# breakout.net
KiCad netlist of a schematic drawn in EAGLE
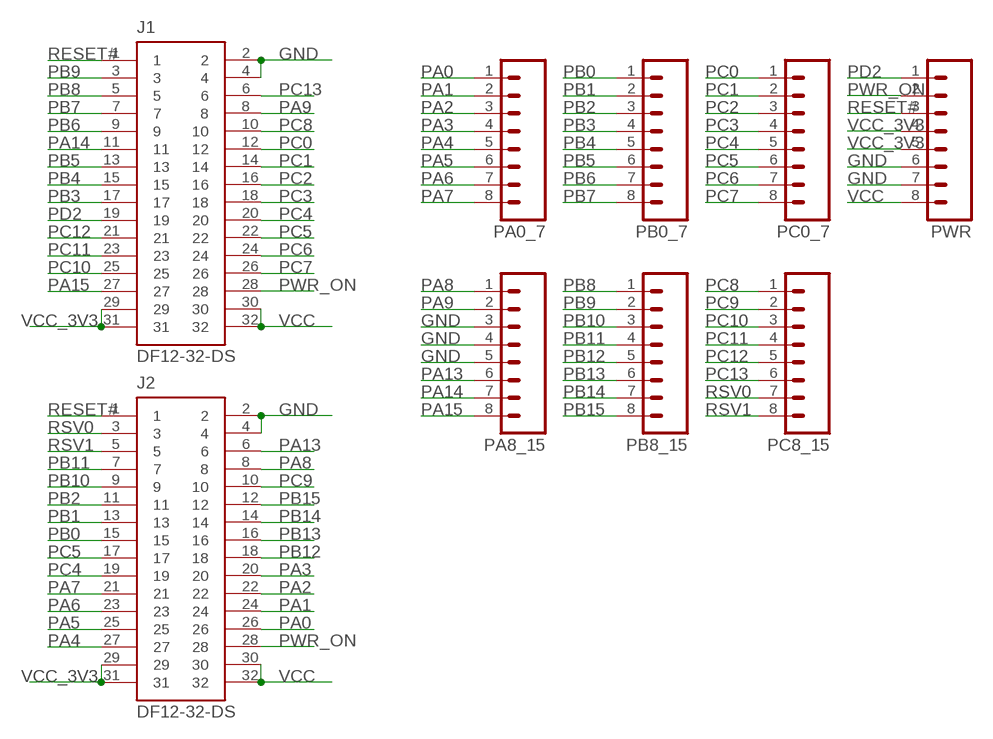
[diagram p0: schematic, sheet 1]

(export (version "E")
  (design (tool "Eeschema 10.0.6"))
  (components
    (comp (ref "J1")
      (value "DF12-32-DS")
      (footprint "eagle-import:DF12-32-DS")
      (fields (field (name "PARTNO") "AS-ITM-00012"))
      (libsource (lib "eagle-import") (part "AS-ITM-00012"))
    )
    (comp (ref "J2")
      (value "DF12-32-DS")
      (footprint "eagle-import:DF12-32-DS")
      (fields (field (name "PARTNO") "AS-ITM-00012"))
      (libsource (lib "eagle-import") (part "AS-ITM-00012"))
    )
    (comp (ref "PA0_7")
      (value "M08FEMALE_LOCK")
      (footprint "eagle-import:1X08_FEMALE_LOCK")
      (libsource (lib "eagle-import") (part "M08FEMALE_LOCK"))
    )
    (comp (ref "PA8_15")
      (value "M08FEMALE_LOCK")
      (footprint "eagle-import:1X08_FEMALE_LOCK")
      (libsource (lib "eagle-import") (part "M08FEMALE_LOCK"))
    )
    (comp (ref "PB0_7")
      (value "M08FEMALE_LOCK")
      (footprint "eagle-import:1X08_FEMALE_LOCK")
      (libsource (lib "eagle-import") (part "M08FEMALE_LOCK"))
    )
    (comp (ref "PB8_15")
      (value "M08FEMALE_LOCK")
      (footprint "eagle-import:1X08_FEMALE_LOCK")
      (libsource (lib "eagle-import") (part "M08FEMALE_LOCK"))
    )
    (comp (ref "PC0_7")
      (value "M08FEMALE_LOCK")
      (footprint "eagle-import:1X08_FEMALE_LOCK")
      (libsource (lib "eagle-import") (part "M08FEMALE_LOCK"))
    )
    (comp (ref "PC8_15")
      (value "M08FEMALE_LOCK")
      (footprint "eagle-import:1X08_FEMALE_LOCK")
      (libsource (lib "eagle-import") (part "M08FEMALE_LOCK"))
    )
    (comp (ref "PWR")
      (value "M08FEMALE_LOCK")
      (footprint "eagle-import:1X08_FEMALE_LOCK")
      (libsource (lib "eagle-import") (part "M08FEMALE_LOCK"))
    )
  )
  (nets
    (net (code "1") (name "/GND") (class "Default")
      (node (ref "J1") (pin "2") (pinfunction "2_2") (pintype "bidirectional"))
      (node (ref "J1") (pin "4") (pinfunction "4_4") (pintype "bidirectional"))
      (node (ref "J2") (pin "2") (pinfunction "2_2") (pintype "bidirectional"))
      (node (ref "J2") (pin "4") (pinfunction "4_4") (pintype "bidirectional"))
      (node (ref "PA8_15") (pin "3") (pinfunction "3_3") (pintype "passive"))
      (node (ref "PA8_15") (pin "4") (pinfunction "4_4") (pintype "passive"))
      (node (ref "PA8_15") (pin "5") (pinfunction "5_5") (pintype "passive"))
      (node (ref "PWR") (pin "6") (pinfunction "6_6") (pintype "passive"))
      (node (ref "PWR") (pin "7") (pinfunction "7_7") (pintype "passive"))
    )
    (net (code "2") (name "/PA0") (class "Default")
      (node (ref "J2") (pin "26") (pinfunction "26_26") (pintype "bidirectional"))
      (node (ref "PA0_7") (pin "1") (pinfunction "1_1") (pintype "passive"))
    )
    (net (code "3") (name "/PA1") (class "Default")
      (node (ref "J2") (pin "24") (pinfunction "24_24") (pintype "bidirectional"))
      (node (ref "PA0_7") (pin "2") (pinfunction "2_2") (pintype "passive"))
    )
    (net (code "4") (name "/PA2") (class "Default")
      (node (ref "J2") (pin "22") (pinfunction "22_22") (pintype "bidirectional"))
      (node (ref "PA0_7") (pin "3") (pinfunction "3_3") (pintype "passive"))
    )
    (net (code "5") (name "/PA3") (class "Default")
      (node (ref "J2") (pin "20") (pinfunction "20_20") (pintype "bidirectional"))
      (node (ref "PA0_7") (pin "4") (pinfunction "4_4") (pintype "passive"))
    )
    (net (code "6") (name "/PA4") (class "Default")
      (node (ref "J2") (pin "27") (pinfunction "27_27") (pintype "bidirectional"))
      (node (ref "PA0_7") (pin "5") (pinfunction "5_5") (pintype "passive"))
    )
    (net (code "7") (name "/PA5") (class "Default")
      (node (ref "J2") (pin "25") (pinfunction "25_25") (pintype "bidirectional"))
      (node (ref "PA0_7") (pin "6") (pinfunction "6_6") (pintype "passive"))
    )
    (net (code "8") (name "/PA6") (class "Default")
      (node (ref "J2") (pin "23") (pinfunction "23_23") (pintype "bidirectional"))
      (node (ref "PA0_7") (pin "7") (pinfunction "7_7") (pintype "passive"))
    )
    (net (code "9") (name "/PA7") (class "Default")
      (node (ref "J2") (pin "21") (pinfunction "21_21") (pintype "bidirectional"))
      (node (ref "PA0_7") (pin "8") (pinfunction "8_8") (pintype "passive"))
    )
    (net (code "10") (name "/PA8") (class "Default")
      (node (ref "J2") (pin "8") (pinfunction "8_8") (pintype "bidirectional"))
      (node (ref "PA8_15") (pin "1") (pinfunction "1_1") (pintype "passive"))
    )
    (net (code "11") (name "/PA9") (class "Default")
      (node (ref "J1") (pin "8") (pinfunction "8_8") (pintype "bidirectional"))
      (node (ref "PA8_15") (pin "2") (pinfunction "2_2") (pintype "passive"))
    )
    (net (code "12") (name "/PA13") (class "Default")
      (node (ref "J2") (pin "6") (pinfunction "6_6") (pintype "bidirectional"))
      (node (ref "PA8_15") (pin "6") (pinfunction "6_6") (pintype "passive"))
    )
    (net (code "13") (name "/PA14") (class "Default")
      (node (ref "J1") (pin "11") (pinfunction "11_11") (pintype "bidirectional"))
      (node (ref "PA8_15") (pin "7") (pinfunction "7_7") (pintype "passive"))
    )
    (net (code "14") (name "/PA15") (class "Default")
      (node (ref "J1") (pin "27") (pinfunction "27_27") (pintype "bidirectional"))
      (node (ref "PA8_15") (pin "8") (pinfunction "8_8") (pintype "passive"))
    )
    (net (code "15") (name "/PB0") (class "Default")
      (node (ref "J2") (pin "15") (pinfunction "15_15") (pintype "bidirectional"))
      (node (ref "PB0_7") (pin "1") (pinfunction "1_1") (pintype "passive"))
    )
    (net (code "16") (name "/PB1") (class "Default")
      (node (ref "J2") (pin "13") (pinfunction "13_13") (pintype "bidirectional"))
      (node (ref "PB0_7") (pin "2") (pinfunction "2_2") (pintype "passive"))
    )
    (net (code "17") (name "/PB2") (class "Default")
      (node (ref "J2") (pin "11") (pinfunction "11_11") (pintype "bidirectional"))
      (node (ref "PB0_7") (pin "3") (pinfunction "3_3") (pintype "passive"))
    )
    (net (code "18") (name "/PB3") (class "Default")
      (node (ref "J1") (pin "17") (pinfunction "17_17") (pintype "bidirectional"))
      (node (ref "PB0_7") (pin "4") (pinfunction "4_4") (pintype "passive"))
    )
    (net (code "19") (name "/PB4") (class "Default")
      (node (ref "J1") (pin "15") (pinfunction "15_15") (pintype "bidirectional"))
      (node (ref "PB0_7") (pin "5") (pinfunction "5_5") (pintype "passive"))
    )
    (net (code "20") (name "/PB5") (class "Default")
      (node (ref "J1") (pin "13") (pinfunction "13_13") (pintype "bidirectional"))
      (node (ref "PB0_7") (pin "6") (pinfunction "6_6") (pintype "passive"))
    )
    (net (code "21") (name "/PB6") (class "Default")
      (node (ref "J1") (pin "9") (pinfunction "9_9") (pintype "bidirectional"))
      (node (ref "PB0_7") (pin "7") (pinfunction "7_7") (pintype "passive"))
    )
    (net (code "22") (name "/PB7") (class "Default")
      (node (ref "J1") (pin "7") (pinfunction "7_7") (pintype "bidirectional"))
      (node (ref "PB0_7") (pin "8") (pinfunction "8_8") (pintype "passive"))
    )
    (net (code "23") (name "/PB8") (class "Default")
      (node (ref "J1") (pin "5") (pinfunction "5_5") (pintype "bidirectional"))
      (node (ref "PB8_15") (pin "1") (pinfunction "1_1") (pintype "passive"))
    )
    (net (code "24") (name "/PB9") (class "Default")
      (node (ref "J1") (pin "3") (pinfunction "3_3") (pintype "bidirectional"))
      (node (ref "PB8_15") (pin "2") (pinfunction "2_2") (pintype "passive"))
    )
    (net (code "25") (name "/PB10") (class "Default")
      (node (ref "J2") (pin "9") (pinfunction "9_9") (pintype "bidirectional"))
      (node (ref "PB8_15") (pin "3") (pinfunction "3_3") (pintype "passive"))
    )
    (net (code "26") (name "/PB11") (class "Default")
      (node (ref "J2") (pin "7") (pinfunction "7_7") (pintype "bidirectional"))
      (node (ref "PB8_15") (pin "4") (pinfunction "4_4") (pintype "passive"))
    )
    (net (code "27") (name "/PB12") (class "Default")
      (node (ref "J2") (pin "18") (pinfunction "18_18") (pintype "bidirectional"))
      (node (ref "PB8_15") (pin "5") (pinfunction "5_5") (pintype "passive"))
    )
    (net (code "28") (name "/PB13") (class "Default")
      (node (ref "J2") (pin "16") (pinfunction "16_16") (pintype "bidirectional"))
      (node (ref "PB8_15") (pin "6") (pinfunction "6_6") (pintype "passive"))
    )
    (net (code "29") (name "/PB14") (class "Default")
      (node (ref "J2") (pin "14") (pinfunction "14_14") (pintype "bidirectional"))
      (node (ref "PB8_15") (pin "7") (pinfunction "7_7") (pintype "passive"))
    )
    (net (code "30") (name "/PB15") (class "Default")
      (node (ref "J2") (pin "12") (pinfunction "12_12") (pintype "bidirectional"))
      (node (ref "PB8_15") (pin "8") (pinfunction "8_8") (pintype "passive"))
    )
    (net (code "31") (name "/PC0") (class "Default")
      (node (ref "J1") (pin "12") (pinfunction "12_12") (pintype "bidirectional"))
      (node (ref "PC0_7") (pin "1") (pinfunction "1_1") (pintype "passive"))
    )
    (net (code "32") (name "/PC1") (class "Default")
      (node (ref "J1") (pin "14") (pinfunction "14_14") (pintype "bidirectional"))
      (node (ref "PC0_7") (pin "2") (pinfunction "2_2") (pintype "passive"))
    )
    (net (code "33") (name "/PC2") (class "Default")
      (node (ref "J1") (pin "16") (pinfunction "16_16") (pintype "bidirectional"))
      (node (ref "PC0_7") (pin "3") (pinfunction "3_3") (pintype "passive"))
    )
    (net (code "34") (name "/PC3") (class "Default")
      (node (ref "J1") (pin "18") (pinfunction "18_18") (pintype "bidirectional"))
      (node (ref "PC0_7") (pin "4") (pinfunction "4_4") (pintype "passive"))
    )
    (net (code "35") (name "/PC4") (class "Default")
      (node (ref "J1") (pin "20") (pinfunction "20_20") (pintype "bidirectional"))
      (node (ref "J2") (pin "19") (pinfunction "19_19") (pintype "bidirectional"))
      (node (ref "PC0_7") (pin "5") (pinfunction "5_5") (pintype "passive"))
    )
    (net (code "36") (name "/PC5") (class "Default")
      (node (ref "J1") (pin "22") (pinfunction "22_22") (pintype "bidirectional"))
      (node (ref "J2") (pin "17") (pinfunction "17_17") (pintype "bidirectional"))
      (node (ref "PC0_7") (pin "6") (pinfunction "6_6") (pintype "passive"))
    )
    (net (code "37") (name "/PC6") (class "Default")
      (node (ref "J1") (pin "24") (pinfunction "24_24") (pintype "bidirectional"))
      (node (ref "PC0_7") (pin "7") (pinfunction "7_7") (pintype "passive"))
    )
    (net (code "38") (name "/PC7") (class "Default")
      (node (ref "J1") (pin "26") (pinfunction "26_26") (pintype "bidirectional"))
      (node (ref "PC0_7") (pin "8") (pinfunction "8_8") (pintype "passive"))
    )
    (net (code "39") (name "/PC8") (class "Default")
      (node (ref "J1") (pin "10") (pinfunction "10_10") (pintype "bidirectional"))
      (node (ref "PC8_15") (pin "1") (pinfunction "1_1") (pintype "passive"))
    )
    (net (code "40") (name "/PC9") (class "Default")
      (node (ref "J2") (pin "10") (pinfunction "10_10") (pintype "bidirectional"))
      (node (ref "PC8_15") (pin "2") (pinfunction "2_2") (pintype "passive"))
    )
    (net (code "41") (name "/PC10") (class "Default")
      (node (ref "J1") (pin "25") (pinfunction "25_25") (pintype "bidirectional"))
      (node (ref "PC8_15") (pin "3") (pinfunction "3_3") (pintype "passive"))
    )
    (net (code "42") (name "/PC11") (class "Default")
      (node (ref "J1") (pin "23") (pinfunction "23_23") (pintype "bidirectional"))
      (node (ref "PC8_15") (pin "4") (pinfunction "4_4") (pintype "passive"))
    )
    (net (code "43") (name "/PC12") (class "Default")
      (node (ref "J1") (pin "21") (pinfunction "21_21") (pintype "bidirectional"))
      (node (ref "PC8_15") (pin "5") (pinfunction "5_5") (pintype "passive"))
    )
    (net (code "44") (name "/PC13") (class "Default")
      (node (ref "J1") (pin "6") (pinfunction "6_6") (pintype "bidirectional"))
      (node (ref "PC8_15") (pin "6") (pinfunction "6_6") (pintype "passive"))
    )
    (net (code "45") (name "/PD2") (class "Default")
      (node (ref "J1") (pin "19") (pinfunction "19_19") (pintype "bidirectional"))
      (node (ref "PWR") (pin "1") (pinfunction "1_1") (pintype "passive"))
    )
    (net (code "46") (name "/PWR_ON") (class "Default")
      (node (ref "J1") (pin "28") (pinfunction "28_28") (pintype "bidirectional"))
      (node (ref "J2") (pin "28") (pinfunction "28_28") (pintype "bidirectional"))
      (node (ref "PWR") (pin "2") (pinfunction "2_2") (pintype "passive"))
    )
    (net (code "47") (name "/RESET#") (class "Default")
      (node (ref "J1") (pin "1") (pinfunction "1_1") (pintype "bidirectional"))
      (node (ref "J2") (pin "1") (pinfunction "1_1") (pintype "bidirectional"))
      (node (ref "PWR") (pin "3") (pinfunction "3_3") (pintype "passive"))
    )
    (net (code "48") (name "/RSV0") (class "Default")
      (node (ref "J2") (pin "3") (pinfunction "3_3") (pintype "bidirectional"))
      (node (ref "PC8_15") (pin "7") (pinfunction "7_7") (pintype "passive"))
    )
    (net (code "49") (name "/RSV1") (class "Default")
      (node (ref "J2") (pin "5") (pinfunction "5_5") (pintype "bidirectional"))
      (node (ref "PC8_15") (pin "8") (pinfunction "8_8") (pintype "passive"))
    )
    (net (code "50") (name "/VCC") (class "Default")
      (node (ref "J1") (pin "30") (pinfunction "30_30") (pintype "bidirectional"))
      (node (ref "J1") (pin "32") (pinfunction "32_32") (pintype "bidirectional"))
      (node (ref "J2") (pin "30") (pinfunction "30_30") (pintype "bidirectional"))
      (node (ref "J2") (pin "32") (pinfunction "32_32") (pintype "bidirectional"))
      (node (ref "PWR") (pin "8") (pinfunction "8_8") (pintype "passive"))
    )
    (net (code "51") (name "/VCC_3V3") (class "Default")
      (node (ref "J1") (pin "29") (pinfunction "29_29") (pintype "bidirectional"))
      (node (ref "J1") (pin "31") (pinfunction "31_31") (pintype "bidirectional"))
      (node (ref "J2") (pin "29") (pinfunction "29_29") (pintype "bidirectional"))
      (node (ref "J2") (pin "31") (pinfunction "31_31") (pintype "bidirectional"))
      (node (ref "PWR") (pin "4") (pinfunction "4_4") (pintype "passive"))
      (node (ref "PWR") (pin "5") (pinfunction "5_5") (pintype "passive"))
    )
  )
)
